# CAN.net
KiCad netlist of a schematic drawn in Altium Designer
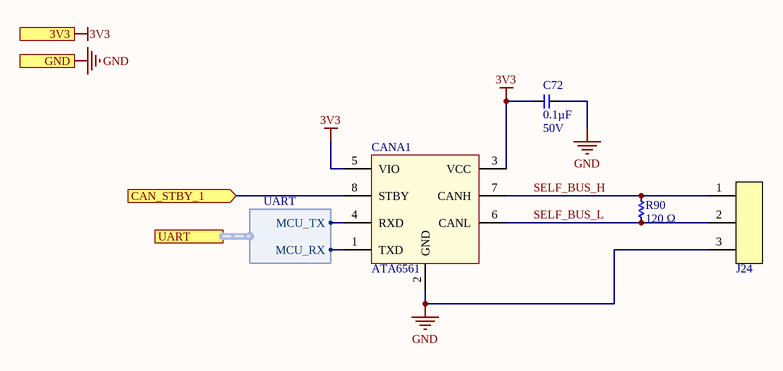
[diagram p0: CAN.SchDoc]

(export (version "E")
  (design (tool "Eeschema 10.0.6"))
  (components
    (comp (ref "C72")
      (value "490-1519-1-ND")
      (footprint "C0603")
      (description "CAP CER 0603 0.1µF X7R 50V 10%")
      (fields
        (field (name "CAPACITANCE (SHORTHAND)") "0.1µF")
        (field (name "MANUFACTURER") "Murata Electronics North America")
        (field (name "RATED VOLTAGE") "50V")
      )
      (libsource (lib "Stanford Student Space Initiative") (part "__template_cap"))
    )
    (comp (ref "CANA1")
      (value "ATA6561")
      (footprint "8SOIC150")
      (description "Atmel CAN Bus Transciever")
      (libsource (lib "Stanford Student Space Initiative") (part "ATA6561"))
    )
    (comp (ref "J24")
      (value "CONN_1x3")
      (footprint "CONN_1x3_100MIL")
      (description "CONN HEADER 3POS T/H")
      (fields
        (field (name "MANUFACTURER PART NUMBER") "61300311121")
        (field (name "MANUFACTURER") "Wurth Electronics")
      )
      (libsource (lib "Stanford Student Space Initiative") (part "Symbol"))
    )
    (comp (ref "R90")
      (value "311-120HRCT-ND")
      (footprint "R0603")
      (description "RES SMD 120 OHM 1% 1/10W 0603")
      (fields
        (field (name "RESISTANCE") "120 Ω")
        (field (name "MANUFACTURER PART NUMBER") "RC0603FR-07120RL")
        (field (name "MANUFACTURER") "Yageo")
      )
      (libsource (lib "Stanford Student Space Initiative") (part "__template_resistor"))
    )
  )
  (nets
    (net (code "2") (name "/CAN_STBY_1") (class "Default")
      (node (ref "CANA1") (pin "8") (pinfunction "STBY_8") (pintype "passive"))
    )
    (net (code "3") (name "/MCU_RX") (class "Default")
      (node (ref "CANA1") (pin "1") (pinfunction "TXD_1") (pintype "passive"))
    )
    (net (code "4") (name "/MCU_TX") (class "Default")
      (node (ref "CANA1") (pin "4") (pinfunction "RXD_4") (pintype "passive"))
    )
    (net (code "5") (name "/SELF_BUS_H") (class "Default")
      (node (ref "CANA1") (pin "7") (pinfunction "CANH_7") (pintype "passive"))
      (node (ref "J24") (pin "1") (pinfunction "1_1") (pintype "passive"))
      (node (ref "R90") (pin "2") (pinfunction "2_2") (pintype "passive"))
    )
    (net (code "6") (name "/SELF_BUS_L") (class "Default")
      (node (ref "CANA1") (pin "6") (pinfunction "CANL_6") (pintype "passive"))
      (node (ref "J24") (pin "2") (pinfunction "2_2") (pintype "passive"))
      (node (ref "R90") (pin "1") (pinfunction "1_1") (pintype "passive"))
    )
    (net (code "8") (name "3V3") (class "Default")
      (node (ref "C72") (pin "2") (pintype "passive"))
      (node (ref "CANA1") (pin "3") (pinfunction "VCC_3") (pintype "passive"))
      (node (ref "CANA1") (pin "5") (pinfunction "VIO_5") (pintype "passive"))
    )
    (net (code "9") (name "GND") (class "Default")
      (node (ref "C72") (pin "1") (pintype "passive"))
      (node (ref "CANA1") (pin "2") (pinfunction "GND_2") (pintype "passive"))
      (node (ref "J24") (pin "3") (pinfunction "3_3") (pintype "passive"))
    )
  )
)
